# Cover_Sheet.net
KiCad netlist of a schematic drawn in Altium Designer
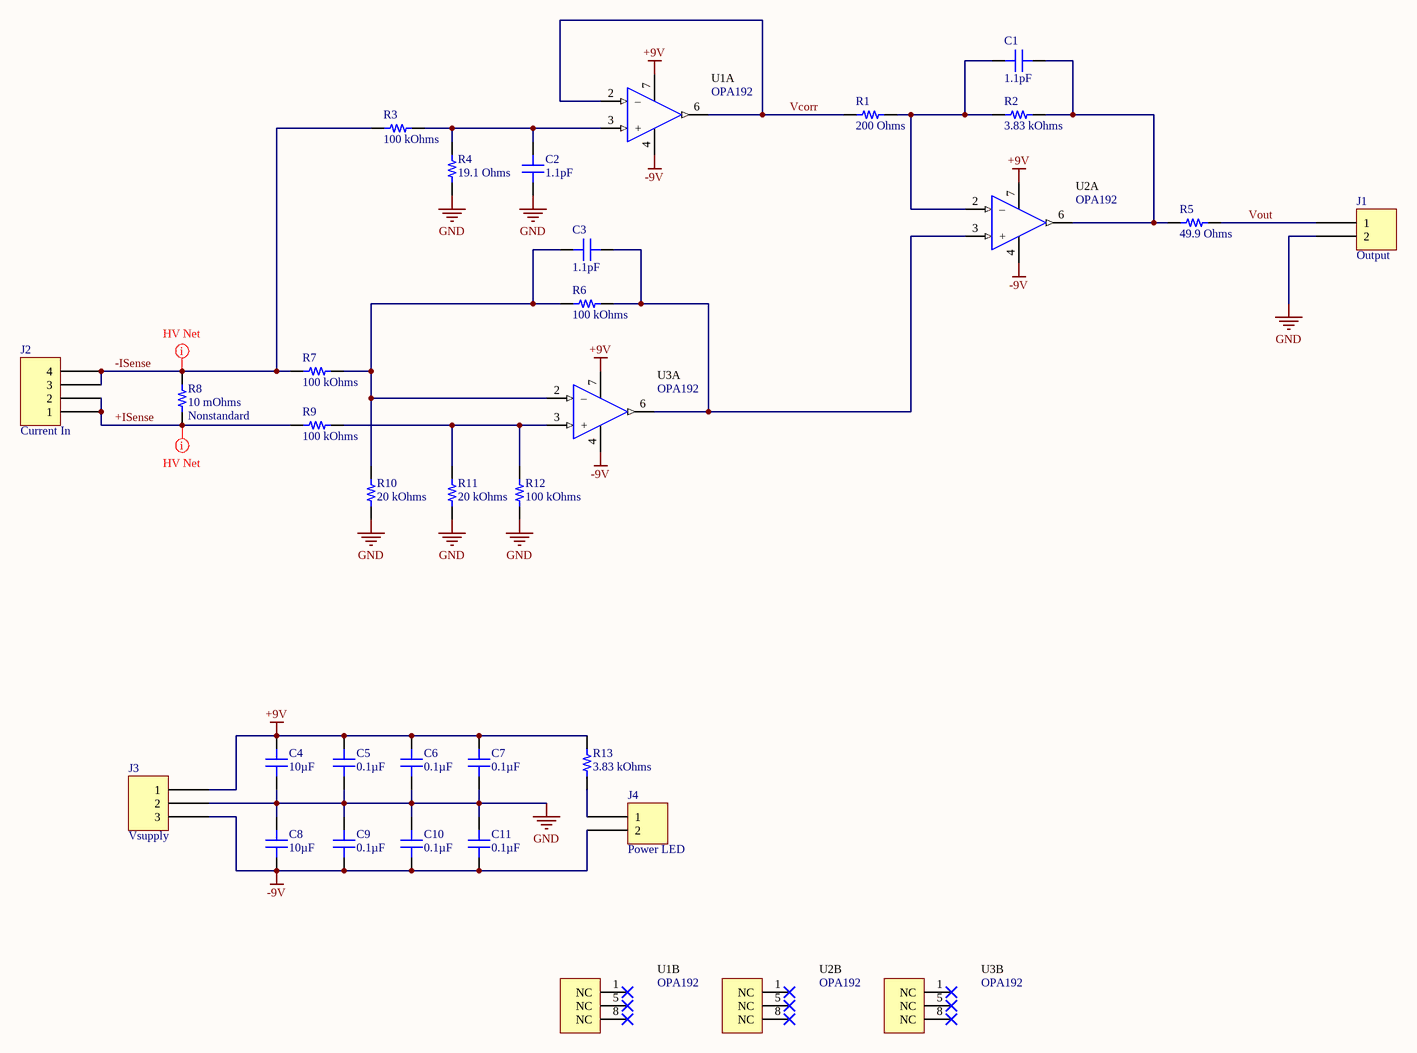
[diagram p0: Cover Sheet.SchDoc]

(export (version "E")
  (design (tool "Eeschema 10.0.6"))
  (components
    (comp (ref "C1")
      (value "1.1pF")
      (footprint "CAP 0805_2012")
      (description "CAP CER 1.1PF 250V C0G/NP0 0805")
      (fields
        (field (name "PART NUMBER") "600F1R1BT250XT")
        (field (name "MANUFACTURER") "American Technical Ceramics")
      )
      (libsource (lib "Celestial Altium Library - altium_library") (part "Capacitor"))
    )
    (comp (ref "C2")
      (value "1.1pF")
      (footprint "CAP 0805_2012")
      (description "CAP CER 1.1PF 250V C0G/NP0 0805")
      (fields
        (field (name "PART NUMBER") "600F1R1BT250XT")
        (field (name "MANUFACTURER") "American Technical Ceramics")
      )
      (libsource (lib "Celestial Altium Library - altium_library") (part "Capacitor"))
    )
    (comp (ref "C3")
      (value "1.1pF")
      (footprint "CAP 0805_2012")
      (description "CAP CER 1.1PF 250V C0G/NP0 0805")
      (fields
        (field (name "PART NUMBER") "600F1R1BT250XT")
        (field (name "MANUFACTURER") "American Technical Ceramics")
      )
      (libsource (lib "Celestial Altium Library - altium_library") (part "Capacitor"))
    )
    (comp (ref "C4")
      (value "10µF")
      (footprint "CAP 0805_2012")
      (description "CAP CER 10UF 25V X5R 0805")
      (fields
        (field (name "PART NUMBER") "CL21A106KAYNNNE")
        (field (name "MANUFACTURER") "Samsung Electro-Mechanics")
      )
      (libsource (lib "Celestial Altium Library - altium_library") (part "Capacitor"))
    )
    (comp (ref "C5")
      (value "0.1µF")
      (footprint "CAP 0805_2012")
      (description "CAP CER 0.1UF 25V X7R 0805")
      (fields (field (name "PART NUMBER") "CC0805MRX7R8BB104") (field (name "MANUFACTURER") "Yageo"))
      (libsource (lib "Celestial Altium Library - altium_library") (part "Capacitor"))
    )
    (comp (ref "C6")
      (value "0.1µF")
      (footprint "CAP 0805_2012")
      (description "CAP CER 0.1UF 25V X7R 0805")
      (fields (field (name "PART NUMBER") "CC0805MRX7R8BB104") (field (name "MANUFACTURER") "Yageo"))
      (libsource (lib "Celestial Altium Library - altium_library") (part "Capacitor"))
    )
    (comp (ref "C7")
      (value "0.1µF")
      (footprint "CAP 0805_2012")
      (description "CAP CER 0.1UF 25V X7R 0805")
      (fields (field (name "PART NUMBER") "CC0805MRX7R8BB104") (field (name "MANUFACTURER") "Yageo"))
      (libsource (lib "Celestial Altium Library - altium_library") (part "Capacitor"))
    )
    (comp (ref "C8")
      (value "10µF")
      (footprint "CAP 0805_2012")
      (description "CAP CER 10UF 25V X5R 0805")
      (fields
        (field (name "PART NUMBER") "CL21A106KAYNNNE")
        (field (name "MANUFACTURER") "Samsung Electro-Mechanics")
      )
      (libsource (lib "Celestial Altium Library - altium_library") (part "Capacitor"))
    )
    (comp (ref "C9")
      (value "0.1µF")
      (footprint "CAP 0805_2012")
      (description "CAP CER 0.1UF 25V X7R 0805")
      (fields (field (name "PART NUMBER") "CC0805MRX7R8BB104") (field (name "MANUFACTURER") "Yageo"))
      (libsource (lib "Celestial Altium Library - altium_library") (part "Capacitor"))
    )
    (comp (ref "C10")
      (value "0.1µF")
      (footprint "CAP 0805_2012")
      (description "CAP CER 0.1UF 25V X7R 0805")
      (fields (field (name "PART NUMBER") "CC0805MRX7R8BB104") (field (name "MANUFACTURER") "Yageo"))
      (libsource (lib "Celestial Altium Library - altium_library") (part "Capacitor"))
    )
    (comp (ref "C11")
      (value "0.1µF")
      (footprint "CAP 0805_2012")
      (description "CAP CER 0.1UF 25V X7R 0805")
      (fields (field (name "PART NUMBER") "CC0805MRX7R8BB104") (field (name "MANUFACTURER") "Yageo"))
      (libsource (lib "Celestial Altium Library - altium_library") (part "Capacitor"))
    )
    (comp (ref "J1")
      (value "Output")
      (footprint "MOLEX KK 0022272021")
      (description "CONN HEADER VERT 2POS 2.54MM")
      (fields (field (name "PART NUMBER") "0022272021") (field (name "MANUFACTURER") "Molex"))
      (libsource (lib "Celestial Altium Library - altium_library") (part "2 Pin"))
    )
    (comp (ref "J2")
      (value "Current In")
      (footprint "TE 282834-4")
      (description "TERM BLK 4P SIDE ENT 2.54MM PCB")
      (fields
        (field (name "PART NUMBER") "282834-4")
        (field (name "MANUFACTURER") "TE Connectivity AMP Connectors")
      )
      (libsource (lib "Celestial Altium Library - altium_library") (part "4 Pin"))
    )
    (comp (ref "J3")
      (value "Vsupply")
      (footprint "MOLEX KK 0022272031")
      (description "CONN HEADER VERT 3POS 2.54MM")
      (fields (field (name "PART NUMBER") "0022272031") (field (name "MANUFACTURER") "Molex"))
      (libsource (lib "Celestial Altium Library - altium_library") (part "3 Pin"))
    )
    (comp (ref "J4")
      (value "Power LED")
      (footprint "MOLEX KK 0022272021")
      (description "CONN HEADER VERT 2POS 2.54MM")
      (fields (field (name "PART NUMBER") "0022272021") (field (name "MANUFACTURER") "Molex"))
      (libsource (lib "Celestial Altium Library - altium_library") (part "2 Pin"))
    )
    (comp (ref "R1")
      (value "200 Ohms")
      (footprint "RES 0805_2012")
      (description "RES SMD 200 OHM 0.1% 1/4W 0805")
      (fields
        (field (name "PART NUMBER") "ERJ-PB6B2000V")
        (field (name "MANUFACTURER") "Panasonic Electronic Components")
      )
      (libsource (lib "Celestial Altium Library - altium_library") (part "Resistor"))
    )
    (comp (ref "R2")
      (value "3.83 kOhms")
      (footprint "RES 0805_2012")
      (description "RES SMD 3.83K OHM 0.5% 1/4W 0805")
      (fields
        (field (name "PART NUMBER") "ERJ-PB6D3831V")
        (field (name "MANUFACTURER") "Panasonic Electronic Components")
      )
      (libsource (lib "Celestial Altium Library - altium_library") (part "Resistor"))
    )
    (comp (ref "R3")
      (value "100 kOhms")
      (footprint "RES 0805_2012")
      (description "RES 100K OHM 0.1% 1/8W 0805")
      (fields
        (field (name "PART NUMBER") "ERA-6AEB104V")
        (field (name "MANUFACTURER") "Panasonic Electronic Components")
      )
      (libsource (lib "Celestial Altium Library - altium_library") (part "Resistor"))
    )
    (comp (ref "R4")
      (value "19.1 Ohms")
      (footprint "RES 0805_2012")
      (description "RES SMD 19.1 OHM 0.1% 1/4W 0805")
      (fields
        (field (name "PART NUMBER") "5-1625868-4")
        (field (name "MANUFACTURER") "TE Connectivity Passive Product")
      )
      (libsource (lib "Celestial Altium Library - altium_library") (part "Resistor"))
    )
    (comp (ref "R5")
      (value "49.9 Ohms")
      (footprint "RES 0805_2012")
      (description "RES SMD 49.9 OHM 1% 1/8W 0805")
      (fields
        (field (name "PART NUMBER") "ERJ-6ENF49R9V")
        (field (name "MANUFACTURER") "Panasonic Electronic Components")
      )
      (libsource (lib "Celestial Altium Library - altium_library") (part "Resistor"))
    )
    (comp (ref "R6")
      (value "100 kOhms")
      (footprint "RES 0805_2012")
      (description "RES 100K OHM 0.1% 1/8W 0805")
      (fields
        (field (name "PART NUMBER") "ERA-6AEB104V")
        (field (name "MANUFACTURER") "Panasonic Electronic Components")
      )
      (libsource (lib "Celestial Altium Library - altium_library") (part "Resistor"))
    )
    (comp (ref "R7")
      (value "100 kOhms")
      (footprint "RES 0805_2012")
      (description "RES 100K OHM 0.1% 1/8W 0805")
      (fields
        (field (name "PART NUMBER") "ERA-6AEB104V")
        (field (name "MANUFACTURER") "Panasonic Electronic Components")
      )
      (libsource (lib "Celestial Altium Library - altium_library") (part "Resistor"))
    )
    (comp (ref "R8")
      (value "10 mOhms")
      (footprint "VISHAY WSHP2818")
      (description "RES 0.01 OHM 1% 10W 2818")
      (fields
        (field (name "PART NUMBER") "WSHP2818R0100FEA")
        (field (name "PACKAGE / CASE") "Nonstandard")
        (field (name "MANUFACTURER") "Vishay Dale")
      )
      (libsource (lib "Celestial Altium Library - altium_library") (part "Resistor"))
    )
    (comp (ref "R9")
      (value "100 kOhms")
      (footprint "RES 0805_2012")
      (description "RES 100K OHM 0.1% 1/8W 0805")
      (fields
        (field (name "PART NUMBER") "ERA-6AEB104V")
        (field (name "MANUFACTURER") "Panasonic Electronic Components")
      )
      (libsource (lib "Celestial Altium Library - altium_library") (part "Resistor"))
    )
    (comp (ref "R10")
      (value "20 kOhms")
      (footprint "RES 0805_2012")
      (description "RES 20K OHM 0.05% 1/8W 0805")
      (fields
        (field (name "PART NUMBER") "ERA-6ARW203V")
        (field (name "MANUFACTURER") "Panasonic Electronic Components")
      )
      (libsource (lib "Celestial Altium Library - altium_library") (part "Resistor"))
    )
    (comp (ref "R11")
      (value "20 kOhms")
      (footprint "RES 0805_2012")
      (description "RES 20K OHM 0.05% 1/8W 0805")
      (fields
        (field (name "PART NUMBER") "ERA-6ARW203V")
        (field (name "MANUFACTURER") "Panasonic Electronic Components")
      )
      (libsource (lib "Celestial Altium Library - altium_library") (part "Resistor"))
    )
    (comp (ref "R12")
      (value "100 kOhms")
      (footprint "RES 0805_2012")
      (description "RES 100K OHM 0.1% 1/8W 0805")
      (fields
        (field (name "PART NUMBER") "ERA-6AEB104V")
        (field (name "MANUFACTURER") "Panasonic Electronic Components")
      )
      (libsource (lib "Celestial Altium Library - altium_library") (part "Resistor"))
    )
    (comp (ref "R13")
      (value "3.83 kOhms")
      (footprint "RES 0805_2012")
      (description "RES SMD 3.83K OHM 0.5% 1/4W 0805")
      (fields
        (field (name "PART NUMBER") "ERJ-PB6D3831V")
        (field (name "MANUFACTURER") "Panasonic Electronic Components")
      )
      (libsource (lib "Celestial Altium Library - altium_library") (part "Resistor"))
    )
    (comp (ref "U1")
      (value "OPA192")
      (footprint "SOIC127P600X175-8N")
      (description "Precision, Rail to Rail I/O, Low Vos, Low Ib Op Amp")
      (fields (field (name "MANUFACTURER") "Texas Instruments") (field (name "DESIGNER") "Alex Davis"))
      (libsource (lib "TI_Misc") (part "OPA192ID"))
    )
    (comp (ref "U2")
      (value "OPA192")
      (footprint "SOIC127P600X175-8N")
      (description "Precision, Rail to Rail I/O, Low Vos, Low Ib Op Amp")
      (fields (field (name "MANUFACTURER") "Texas Instruments") (field (name "DESIGNER") "Alex Davis"))
      (libsource (lib "TI_Misc") (part "OPA192ID"))
    )
    (comp (ref "U3")
      (value "OPA192")
      (footprint "SOIC127P600X175-8N")
      (description "Precision, Rail to Rail I/O, Low Vos, Low Ib Op Amp")
      (fields (field (name "MANUFACTURER") "Texas Instruments") (field (name "DESIGNER") "Alex Davis"))
      (libsource (lib "TI_Misc") (part "OPA192ID"))
    )
  )
  (nets
    (net (code "1") (name "+9V") (class "Default")
      (node (ref "C4") (pin "2") (pinfunction "2_2") (pintype "passive"))
      (node (ref "C5") (pin "1") (pinfunction "1_1") (pintype "passive"))
      (node (ref "C6") (pin "1") (pinfunction "1_1") (pintype "passive"))
      (node (ref "C7") (pin "1") (pinfunction "1_1") (pintype "passive"))
      (node (ref "J3") (pin "1") (pinfunction "1_1") (pintype "passive"))
      (node (ref "R13") (pin "2") (pinfunction "2_2") (pintype "passive"))
      (node (ref "U1") (pin "7") (pinfunction "V+_7") (pintype "power_in"))
      (node (ref "U2") (pin "7") (pinfunction "V+_7") (pintype "power_in"))
      (node (ref "U3") (pin "7") (pinfunction "V+_7") (pintype "power_in"))
    )
    (net (code "2") (name "-9V") (class "Default")
      (node (ref "C10") (pin "2") (pinfunction "2_2") (pintype "passive"))
      (node (ref "C11") (pin "2") (pinfunction "2_2") (pintype "passive"))
      (node (ref "C8") (pin "1") (pinfunction "1_1") (pintype "passive"))
      (node (ref "C9") (pin "2") (pinfunction "2_2") (pintype "passive"))
      (node (ref "J3") (pin "3") (pinfunction "3_3") (pintype "passive"))
      (node (ref "J4") (pin "2") (pinfunction "2_2") (pintype "passive"))
      (node (ref "U1") (pin "4") (pinfunction "V-_4") (pintype "power_in"))
      (node (ref "U2") (pin "4") (pinfunction "V-_4") (pintype "power_in"))
      (node (ref "U3") (pin "4") (pinfunction "V-_4") (pintype "power_in"))
    )
    (net (code "3") (name "/+ISense") (class "Default")
      (node (ref "J2") (pin "1") (pinfunction "1_1") (pintype "passive"))
      (node (ref "J2") (pin "2") (pinfunction "2_2") (pintype "passive"))
      (node (ref "R8") (pin "1") (pinfunction "1_1") (pintype "passive"))
      (node (ref "R9") (pin "1") (pinfunction "1_1") (pintype "passive"))
    )
    (net (code "4") (name "/-ISense") (class "Default")
      (node (ref "J2") (pin "3") (pinfunction "3_3") (pintype "passive"))
      (node (ref "J2") (pin "4") (pinfunction "4_4") (pintype "passive"))
      (node (ref "R3") (pin "1") (pinfunction "1_1") (pintype "passive"))
      (node (ref "R7") (pin "1") (pinfunction "1_1") (pintype "passive"))
      (node (ref "R8") (pin "2") (pinfunction "2_2") (pintype "passive"))
    )
    (net (code "5") (name "/Vcorr") (class "Default")
      (node (ref "R1") (pin "1") (pinfunction "1_1") (pintype "passive"))
      (node (ref "U1") (pin "2") (pinfunction "–_2") (pintype "input"))
      (node (ref "U1") (pin "6") (pinfunction "Out_6") (pintype "output"))
    )
    (net (code "6") (name "/Vout") (class "Default")
      (node (ref "J1") (pin "1") (pinfunction "1_1") (pintype "passive"))
      (node (ref "R5") (pin "2") (pinfunction "2_2") (pintype "passive"))
    )
    (net (code "7") (name "GND") (class "Default")
      (node (ref "C10") (pin "1") (pinfunction "1_1") (pintype "passive"))
      (node (ref "C11") (pin "1") (pinfunction "1_1") (pintype "passive"))
      (node (ref "C2") (pin "2") (pinfunction "2_2") (pintype "passive"))
      (node (ref "C4") (pin "1") (pinfunction "1_1") (pintype "passive"))
      (node (ref "C5") (pin "2") (pinfunction "2_2") (pintype "passive"))
      (node (ref "C6") (pin "2") (pinfunction "2_2") (pintype "passive"))
      (node (ref "C7") (pin "2") (pinfunction "2_2") (pintype "passive"))
      (node (ref "C8") (pin "2") (pinfunction "2_2") (pintype "passive"))
      (node (ref "C9") (pin "1") (pinfunction "1_1") (pintype "passive"))
      (node (ref "J1") (pin "2") (pinfunction "2_2") (pintype "passive"))
      (node (ref "J3") (pin "2") (pinfunction "2_2") (pintype "passive"))
      (node (ref "R10") (pin "1") (pinfunction "1_1") (pintype "passive"))
      (node (ref "R11") (pin "1") (pinfunction "1_1") (pintype "passive"))
      (node (ref "R12") (pin "1") (pinfunction "1_1") (pintype "passive"))
      (node (ref "R4") (pin "1") (pinfunction "1_1") (pintype "passive"))
    )
    (net (code "8") (name "Net-(J4-Pad1)") (class "Default")
      (node (ref "J4") (pin "1") (pinfunction "1_1") (pintype "passive"))
      (node (ref "R13") (pin "1") (pinfunction "1_1") (pintype "passive"))
    )
    (net (code "9") (name "Net-(U1A-+)") (class "Default")
      (node (ref "C2") (pin "1") (pinfunction "1_1") (pintype "passive"))
      (node (ref "R3") (pin "2") (pinfunction "2_2") (pintype "passive"))
      (node (ref "R4") (pin "2") (pinfunction "2_2") (pintype "passive"))
      (node (ref "U1") (pin "3") (pinfunction "+_3") (pintype "input"))
    )
    (net (code "10") (name "Net-(U2A-+)") (class "Default")
      (node (ref "C3") (pin "2") (pinfunction "2_2") (pintype "passive"))
      (node (ref "R6") (pin "2") (pinfunction "2_2") (pintype "passive"))
      (node (ref "U2") (pin "3") (pinfunction "+_3") (pintype "input"))
      (node (ref "U3") (pin "6") (pinfunction "Out_6") (pintype "output"))
    )
    (net (code "11") (name "Net-(U2A-Out)") (class "Default")
      (node (ref "C1") (pin "2") (pinfunction "2_2") (pintype "passive"))
      (node (ref "R2") (pin "2") (pinfunction "2_2") (pintype "passive"))
      (node (ref "R5") (pin "1") (pinfunction "1_1") (pintype "passive"))
      (node (ref "U2") (pin "6") (pinfunction "Out_6") (pintype "output"))
    )
    (net (code "12") (name "Net-(U2A-–)") (class "Default")
      (node (ref "C1") (pin "1") (pinfunction "1_1") (pintype "passive"))
      (node (ref "R1") (pin "2") (pinfunction "2_2") (pintype "passive"))
      (node (ref "R2") (pin "1") (pinfunction "1_1") (pintype "passive"))
      (node (ref "U2") (pin "2") (pinfunction "–_2") (pintype "input"))
    )
    (net (code "13") (name "Net-(U3A-+)") (class "Default")
      (node (ref "R11") (pin "2") (pinfunction "2_2") (pintype "passive"))
      (node (ref "R12") (pin "2") (pinfunction "2_2") (pintype "passive"))
      (node (ref "R9") (pin "2") (pinfunction "2_2") (pintype "passive"))
      (node (ref "U3") (pin "3") (pinfunction "+_3") (pintype "input"))
    )
    (net (code "14") (name "Net-(U3A-–)") (class "Default")
      (node (ref "C3") (pin "1") (pinfunction "1_1") (pintype "passive"))
      (node (ref "R10") (pin "2") (pinfunction "2_2") (pintype "passive"))
      (node (ref "R6") (pin "1") (pinfunction "1_1") (pintype "passive"))
      (node (ref "R7") (pin "2") (pinfunction "2_2") (pintype "passive"))
      (node (ref "U3") (pin "2") (pinfunction "–_2") (pintype "input"))
    )
    (net (code "15") (name "unconnected-(U1B-NC-Pad1)") (class "Default")
      (node (ref "U1") (pin "1") (pinfunction "NC_1") (pintype "passive+no_connect"))
    )
    (net (code "16") (name "unconnected-(U1B-NC-Pad5)") (class "Default")
      (node (ref "U1") (pin "5") (pinfunction "NC_5") (pintype "passive+no_connect"))
    )
    (net (code "17") (name "unconnected-(U1B-NC-Pad8)") (class "Default")
      (node (ref "U1") (pin "8") (pinfunction "NC_8") (pintype "passive+no_connect"))
    )
    (net (code "18") (name "unconnected-(U2B-NC-Pad1)") (class "Default")
      (node (ref "U2") (pin "1") (pinfunction "NC_1") (pintype "passive+no_connect"))
    )
    (net (code "19") (name "unconnected-(U2B-NC-Pad5)") (class "Default")
      (node (ref "U2") (pin "5") (pinfunction "NC_5") (pintype "passive+no_connect"))
    )
    (net (code "20") (name "unconnected-(U2B-NC-Pad8)") (class "Default")
      (node (ref "U2") (pin "8") (pinfunction "NC_8") (pintype "passive+no_connect"))
    )
    (net (code "21") (name "unconnected-(U3B-NC-Pad1)") (class "Default")
      (node (ref "U3") (pin "1") (pinfunction "NC_1") (pintype "passive+no_connect"))
    )
    (net (code "22") (name "unconnected-(U3B-NC-Pad5)") (class "Default")
      (node (ref "U3") (pin "5") (pinfunction "NC_5") (pintype "passive+no_connect"))
    )
    (net (code "23") (name "unconnected-(U3B-NC-Pad8)") (class "Default")
      (node (ref "U3") (pin "8") (pinfunction "NC_8") (pintype "passive+no_connect"))
    )
  )
)
